# 10BASE-T1L_2.net
KiCad netlist of a schematic drawn in EAGLE
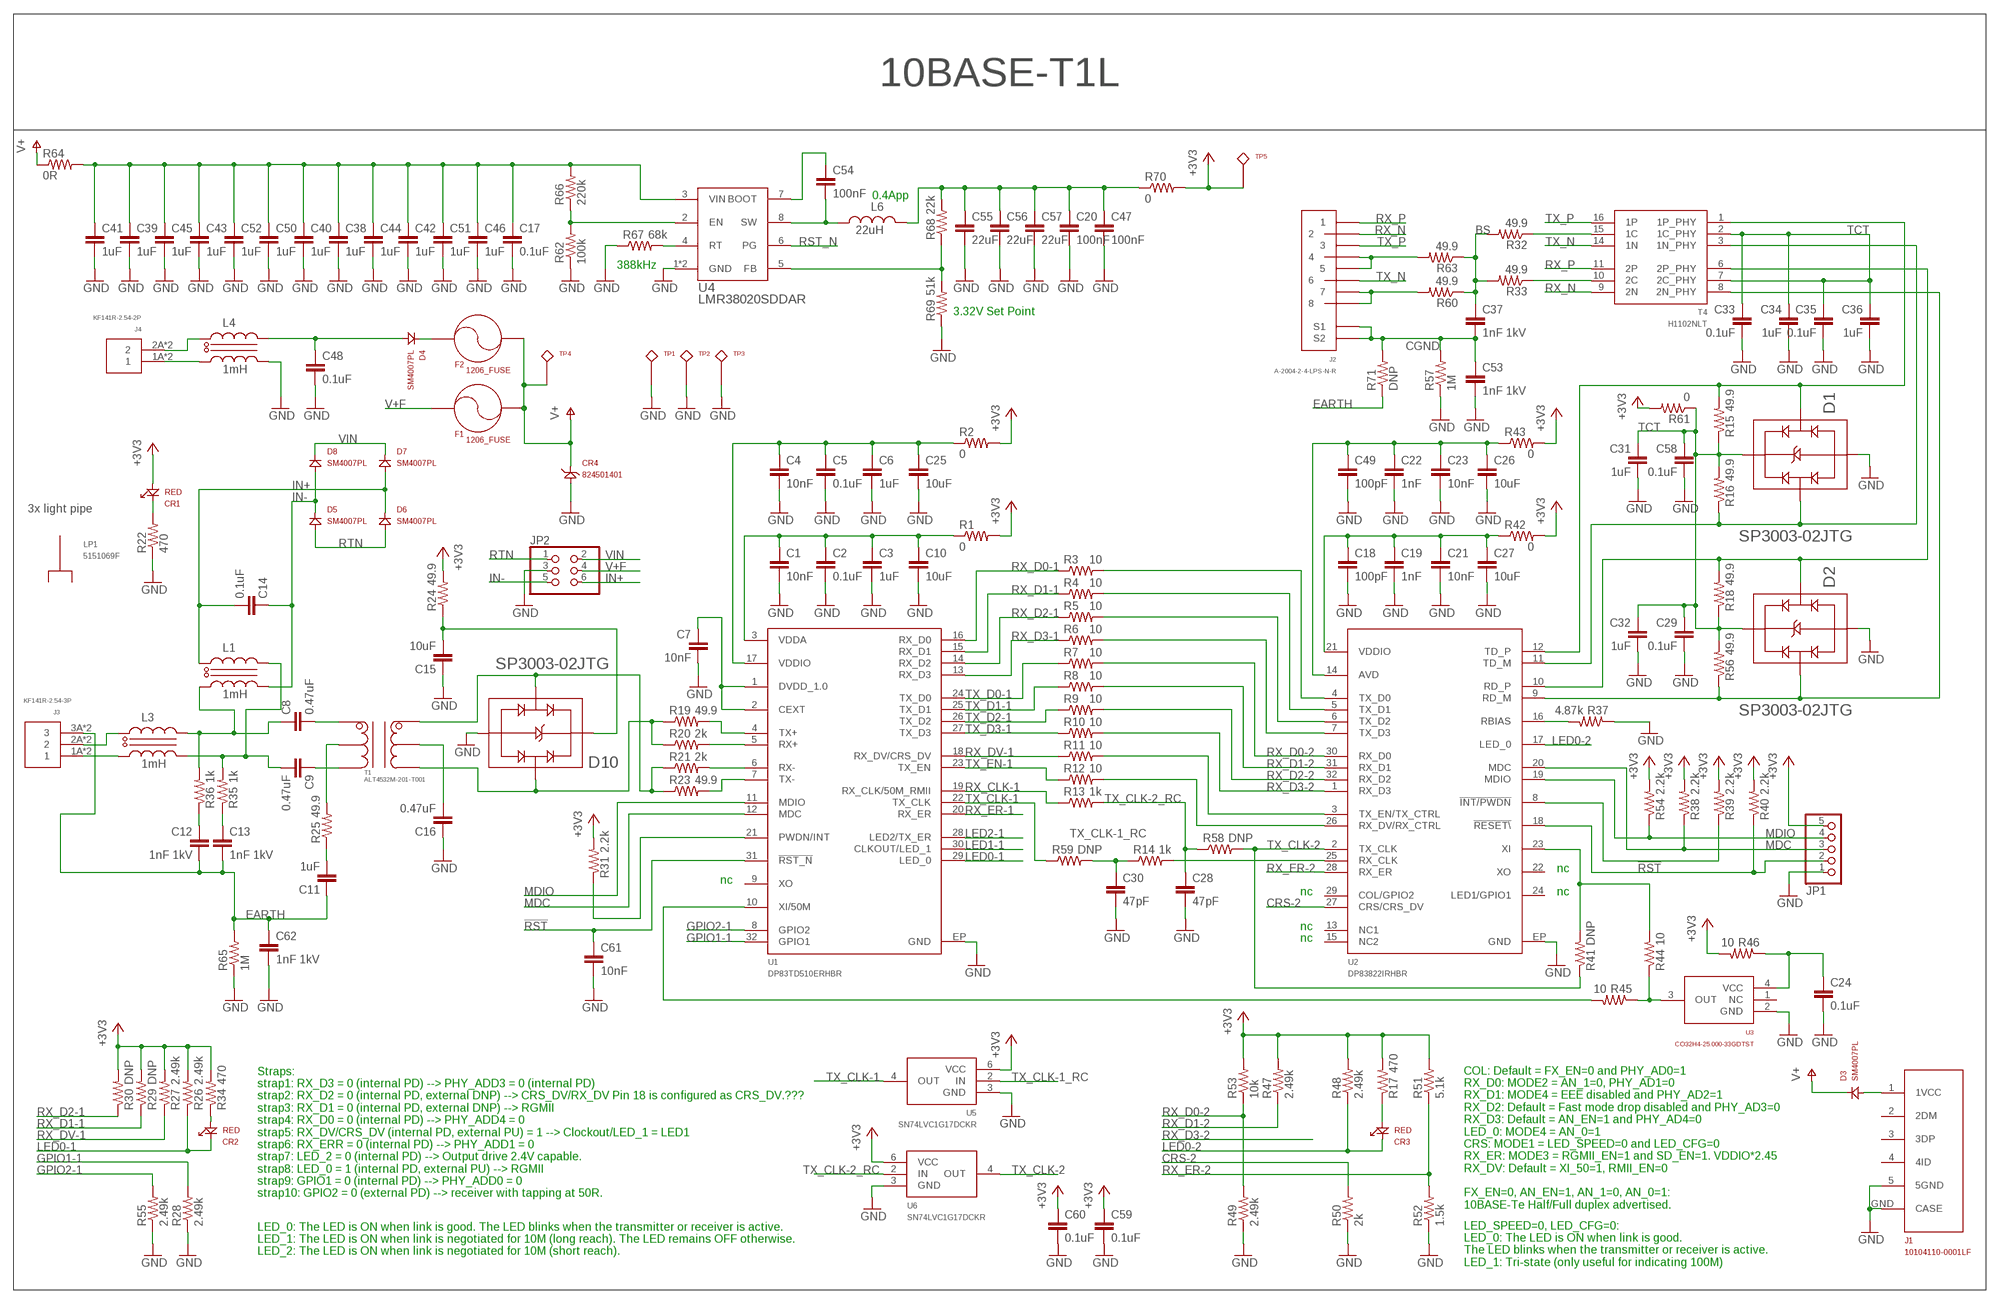
[diagram p0: schematic, sheet 1]

(export (version "E")
  (design (tool "Eeschema 10.0.6"))
  (components
    (comp (ref "C1")
      (value "10nF")
      (footprint "eagle-import:0402_INDUCTOR")
      (libsource (lib "eagle-import") (part "0402_CAPACITOR"))
    )
    (comp (ref "C2")
      (value "0.1uF")
      (footprint "eagle-import:0402_INDUCTOR")
      (libsource (lib "eagle-import") (part "0402_CAPACITOR"))
    )
    (comp (ref "C3")
      (value "1uF")
      (footprint "eagle-import:0402_INDUCTOR")
      (libsource (lib "eagle-import") (part "0402_CAPACITOR"))
    )
    (comp (ref "C4")
      (value "10nF")
      (footprint "eagle-import:0402_INDUCTOR")
      (libsource (lib "eagle-import") (part "0402_CAPACITOR"))
    )
    (comp (ref "C5")
      (value "0.1uF")
      (footprint "eagle-import:0402_INDUCTOR")
      (libsource (lib "eagle-import") (part "0402_CAPACITOR"))
    )
    (comp (ref "C6")
      (value "1uF")
      (footprint "eagle-import:0402_INDUCTOR")
      (libsource (lib "eagle-import") (part "0402_CAPACITOR"))
    )
    (comp (ref "C7")
      (value "10nF")
      (footprint "eagle-import:0402_INDUCTOR")
      (libsource (lib "eagle-import") (part "0402_CAPACITOR"))
    )
    (comp (ref "C8")
      (value "0.47uF")
      (footprint "eagle-import:0603")
      (libsource (lib "eagle-import") (part "0603_CAPACITOR"))
    )
    (comp (ref "C9")
      (value "0.47uF")
      (footprint "eagle-import:0603")
      (libsource (lib "eagle-import") (part "0603_CAPACITOR"))
    )
    (comp (ref "C10")
      (value "10uF")
      (footprint "eagle-import:0603")
      (libsource (lib "eagle-import") (part "0603_CAPACITOR"))
    )
    (comp (ref "C11")
      (value "1uF")
      (footprint "eagle-import:0603")
      (libsource (lib "eagle-import") (part "0603_CAPACITOR"))
    )
    (comp (ref "C12")
      (value "1nF 1kV")
      (footprint "eagle-import:C1206")
      (libsource (lib "eagle-import") (part "C-EUC1206"))
    )
    (comp (ref "C13")
      (value "1nF 1kV")
      (footprint "eagle-import:C1206")
      (libsource (lib "eagle-import") (part "C-EUC1206"))
    )
    (comp (ref "C14")
      (value "0.1uF")
      (footprint "eagle-import:0603")
      (libsource (lib "eagle-import") (part "0603_CAPACITOR"))
    )
    (comp (ref "C15")
      (value "10uF")
      (footprint "eagle-import:0603")
      (libsource (lib "eagle-import") (part "0603_CAPACITOR"))
    )
    (comp (ref "C16")
      (value "0.47uF")
      (footprint "eagle-import:0603")
      (libsource (lib "eagle-import") (part "0603_CAPACITOR"))
    )
    (comp (ref "C17")
      (value "0.1uF")
      (footprint "eagle-import:0603")
      (libsource (lib "eagle-import") (part "0603_CAPACITOR"))
    )
    (comp (ref "C18")
      (value "100pF")
      (footprint "eagle-import:0402_INDUCTOR")
      (libsource (lib "eagle-import") (part "0402_CAPACITOR"))
    )
    (comp (ref "C19")
      (value "1nF")
      (footprint "eagle-import:0402_INDUCTOR")
      (libsource (lib "eagle-import") (part "0402_CAPACITOR"))
    )
    (comp (ref "C20")
      (value "100nF")
      (footprint "eagle-import:0603")
      (libsource (lib "eagle-import") (part "0603_CAPACITOR"))
    )
    (comp (ref "C21")
      (value "10nF")
      (footprint "eagle-import:0402_INDUCTOR")
      (libsource (lib "eagle-import") (part "0402_CAPACITOR"))
    )
    (comp (ref "C22")
      (value "1nF")
      (footprint "eagle-import:0402_INDUCTOR")
      (libsource (lib "eagle-import") (part "0402_CAPACITOR"))
    )
    (comp (ref "C23")
      (value "10nF")
      (footprint "eagle-import:0402_INDUCTOR")
      (libsource (lib "eagle-import") (part "0402_CAPACITOR"))
    )
    (comp (ref "C24")
      (value "0.1uF")
      (footprint "eagle-import:0402_INDUCTOR")
      (libsource (lib "eagle-import") (part "0402_CAPACITOR"))
    )
    (comp (ref "C25")
      (value "10uF")
      (footprint "eagle-import:0603")
      (libsource (lib "eagle-import") (part "0603_CAPACITOR"))
    )
    (comp (ref "C26")
      (value "10uF")
      (footprint "eagle-import:0603")
      (libsource (lib "eagle-import") (part "0603_CAPACITOR"))
    )
    (comp (ref "C27")
      (value "10uF")
      (footprint "eagle-import:0603")
      (libsource (lib "eagle-import") (part "0603_CAPACITOR"))
    )
    (comp (ref "C28")
      (value "47pF")
      (footprint "eagle-import:0402_INDUCTOR")
      (libsource (lib "eagle-import") (part "0402_CAPACITOR"))
    )
    (comp (ref "C29")
      (value "0.1uF")
      (footprint "eagle-import:0402_INDUCTOR")
      (libsource (lib "eagle-import") (part "0402_CAPACITOR"))
    )
    (comp (ref "C30")
      (value "47pF")
      (footprint "eagle-import:0402_INDUCTOR")
      (libsource (lib "eagle-import") (part "0402_CAPACITOR"))
    )
    (comp (ref "C31")
      (value "1uF")
      (footprint "eagle-import:0402_INDUCTOR")
      (libsource (lib "eagle-import") (part "0402_CAPACITOR"))
    )
    (comp (ref "C32")
      (value "1uF")
      (footprint "eagle-import:0402_INDUCTOR")
      (libsource (lib "eagle-import") (part "0402_CAPACITOR"))
    )
    (comp (ref "C33")
      (value "0.1uF")
      (footprint "eagle-import:0402_INDUCTOR")
      (libsource (lib "eagle-import") (part "0402_CAPACITOR"))
    )
    (comp (ref "C34")
      (value "1uF")
      (footprint "eagle-import:0402_INDUCTOR")
      (libsource (lib "eagle-import") (part "0402_CAPACITOR"))
    )
    (comp (ref "C35")
      (value "0.1uF")
      (footprint "eagle-import:0402_INDUCTOR")
      (libsource (lib "eagle-import") (part "0402_CAPACITOR"))
    )
    (comp (ref "C36")
      (value "1uF")
      (footprint "eagle-import:0402_INDUCTOR")
      (libsource (lib "eagle-import") (part "0402_CAPACITOR"))
    )
    (comp (ref "C37")
      (value "1nF 1kV")
      (footprint "eagle-import:C1206")
      (libsource (lib "eagle-import") (part "C-EUC1206"))
    )
    (comp (ref "C38")
      (value "1uF")
      (footprint "eagle-import:C1206")
      (libsource (lib "eagle-import") (part "C-EUC1206"))
    )
    (comp (ref "C39")
      (value "1uF")
      (footprint "eagle-import:C1206")
      (libsource (lib "eagle-import") (part "C-EUC1206"))
    )
    (comp (ref "C40")
      (value "1uF")
      (footprint "eagle-import:C1206")
      (libsource (lib "eagle-import") (part "C-EUC1206"))
    )
    (comp (ref "C41")
      (value "1uF")
      (footprint "eagle-import:C1206")
      (libsource (lib "eagle-import") (part "C-EUC1206"))
    )
    (comp (ref "C42")
      (value "1uF")
      (footprint "eagle-import:C1206")
      (libsource (lib "eagle-import") (part "C-EUC1206"))
    )
    (comp (ref "C43")
      (value "1uF")
      (footprint "eagle-import:C1206")
      (libsource (lib "eagle-import") (part "C-EUC1206"))
    )
    (comp (ref "C44")
      (value "1uF")
      (footprint "eagle-import:C1206")
      (libsource (lib "eagle-import") (part "C-EUC1206"))
    )
    (comp (ref "C45")
      (value "1uF")
      (footprint "eagle-import:C1206")
      (libsource (lib "eagle-import") (part "C-EUC1206"))
    )
    (comp (ref "C46")
      (value "1uF")
      (footprint "eagle-import:C1206")
      (libsource (lib "eagle-import") (part "C-EUC1206"))
    )
    (comp (ref "C47")
      (value "100nF")
      (footprint "eagle-import:0603")
      (libsource (lib "eagle-import") (part "0603_CAPACITOR"))
    )
    (comp (ref "C48")
      (value "0.1uF")
      (footprint "eagle-import:0603")
      (libsource (lib "eagle-import") (part "0603_CAPACITOR"))
    )
    (comp (ref "C49")
      (value "100pF")
      (footprint "eagle-import:0402_INDUCTOR")
      (libsource (lib "eagle-import") (part "0402_CAPACITOR"))
    )
    (comp (ref "C50")
      (value "1uF")
      (footprint "eagle-import:C1206")
      (libsource (lib "eagle-import") (part "C-EUC1206"))
    )
    (comp (ref "C51")
      (value "1uF")
      (footprint "eagle-import:C1206")
      (libsource (lib "eagle-import") (part "C-EUC1206"))
    )
    (comp (ref "C52")
      (value "1uF")
      (footprint "eagle-import:C1206")
      (libsource (lib "eagle-import") (part "C-EUC1206"))
    )
    (comp (ref "C53")
      (value "1nF 1kV")
      (footprint "eagle-import:C1206")
      (libsource (lib "eagle-import") (part "C-EUC1206"))
    )
    (comp (ref "C54")
      (value "100nF")
      (footprint "eagle-import:0603")
      (libsource (lib "eagle-import") (part "0603_CAPACITOR"))
    )
    (comp (ref "C55")
      (value "22uF")
      (footprint "eagle-import:C1206")
      (libsource (lib "eagle-import") (part "C-EUC1206"))
    )
    (comp (ref "C56")
      (value "22uF")
      (footprint "eagle-import:C1206")
      (libsource (lib "eagle-import") (part "C-EUC1206"))
    )
    (comp (ref "C57")
      (value "22uF")
      (footprint "eagle-import:C1206")
      (libsource (lib "eagle-import") (part "C-EUC1206"))
    )
    (comp (ref "C58")
      (value "0.1uF")
      (footprint "eagle-import:0402_INDUCTOR")
      (libsource (lib "eagle-import") (part "0402_CAPACITOR"))
    )
    (comp (ref "C59")
      (value "0.1uF")
      (footprint "eagle-import:0402_INDUCTOR")
      (libsource (lib "eagle-import") (part "0402_CAPACITOR"))
    )
    (comp (ref "C60")
      (value "0.1uF")
      (footprint "eagle-import:0402_INDUCTOR")
      (libsource (lib "eagle-import") (part "0402_CAPACITOR"))
    )
    (comp (ref "C61")
      (value "10nF")
      (footprint "eagle-import:0402_INDUCTOR")
      (libsource (lib "eagle-import") (part "0402_CAPACITOR"))
    )
    (comp (ref "C62")
      (value "1nF 1kV")
      (footprint "eagle-import:C1206")
      (libsource (lib "eagle-import") (part "C-EUC1206"))
    )
    (comp (ref "CR1")
      (value "RED")
      (footprint "eagle-import:0603_DIODE")
      (fields (field (name "PARTNO") "732-4978-1-ND"))
      (libsource (lib "eagle-import") (part "150060RS75000"))
    )
    (comp (ref "CR2")
      (value "RED")
      (footprint "eagle-import:0603_DIODE")
      (fields (field (name "PARTNO") "732-4978-1-ND"))
      (libsource (lib "eagle-import") (part "150060RS75000"))
    )
    (comp (ref "CR3")
      (value "RED")
      (footprint "eagle-import:0603_DIODE")
      (fields (field (name "PARTNO") "732-4978-1-ND"))
      (libsource (lib "eagle-import") (part "150060RS75000"))
    )
    (comp (ref "CR4")
      (value "824501401")
      (footprint "eagle-import:DO-214AC")
      (fields (field (name "PARTNO") "732-9960-1-ND"))
      (libsource (lib "eagle-import") (part "824501401"))
    )
    (comp (ref "D1")
      (value "SP3003-02JTG")
      (footprint "eagle-import:SC-70-5")
      (fields (field (name "PARTNO") "F3301CT-ND"))
      (libsource (lib "eagle-import") (part "SP3003-02JTG"))
    )
    (comp (ref "D2")
      (value "SP3003-02JTG")
      (footprint "eagle-import:SC-70-5")
      (fields (field (name "PARTNO") "F3301CT-ND"))
      (libsource (lib "eagle-import") (part "SP3003-02JTG"))
    )
    (comp (ref "D3")
      (value "SM4007PL")
      (footprint "eagle-import:SOD123(AK)")
      (libsource (lib "eagle-import") (part "SM4007PL"))
    )
    (comp (ref "D4")
      (value "SM4007PL")
      (footprint "eagle-import:SOD123(AK)")
      (libsource (lib "eagle-import") (part "SM4007PL"))
    )
    (comp (ref "D5")
      (value "SM4007PL")
      (footprint "eagle-import:SOD123(AK)")
      (libsource (lib "eagle-import") (part "SM4007PL"))
    )
    (comp (ref "D6")
      (value "SM4007PL")
      (footprint "eagle-import:SOD123(AK)")
      (libsource (lib "eagle-import") (part "SM4007PL"))
    )
    (comp (ref "D7")
      (value "SM4007PL")
      (footprint "eagle-import:SOD123(AK)")
      (libsource (lib "eagle-import") (part "SM4007PL"))
    )
    (comp (ref "D8")
      (value "SM4007PL")
      (footprint "eagle-import:SOD123(AK)")
      (libsource (lib "eagle-import") (part "SM4007PL"))
    )
    (comp (ref "D10")
      (value "SP3003-02JTG")
      (footprint "eagle-import:SC-70-5")
      (fields (field (name "PARTNO") "F3301CT-ND"))
      (libsource (lib "eagle-import") (part "SP3003-02JTG"))
    )
    (comp (ref "F1")
      (value "1206_FUSE")
      (footprint "eagle-import:1206")
      (libsource (lib "eagle-import") (part "1206_FUSE"))
    )
    (comp (ref "F2")
      (value "1206_FUSE")
      (footprint "eagle-import:1206")
      (libsource (lib "eagle-import") (part "1206_FUSE"))
    )
    (comp (ref "J1")
      (value "10104110-0001LF")
      (footprint "eagle-import:MICRO_USB")
      (fields (field (name "PARTNO") "609-4052-1-ND"))
      (libsource (lib "eagle-import") (part "10104110-0001LF"))
    )
    (comp (ref "J2")
      (value "A-2004-2-4-LPS-N-R")
      (footprint "eagle-import:A-2004-2-4-LPS-N-R")
      (fields (field (name "PARTNO") "AE10387-ND"))
      (libsource (lib "eagle-import") (part "A-2004-2-4-LPS-N-R"))
    )
    (comp (ref "J3")
      (value "KF141R-2.54-3P")
      (footprint "eagle-import:KF141R-2.54-3P")
      (libsource (lib "eagle-import") (part "KF141R-2.54-3P"))
    )
    (comp (ref "J4")
      (value "KF141R-2.54-2P")
      (footprint "eagle-import:KF141R-2.54-2P")
      (libsource (lib "eagle-import") (part "KF141R-2.54-2P"))
    )
    (comp (ref "JP1")
      (value "PINHD-1X5")
      (footprint "eagle-import:1X05")
      (libsource (lib "eagle-import") (part "PINHD-1X5"))
    )
    (comp (ref "JP2")
      (value "PINHD-2X3")
      (footprint "eagle-import:2X03")
      (libsource (lib "eagle-import") (part "PINHD-2X3"))
    )
    (comp (ref "L1")
      (value "1mH")
      (footprint "eagle-import:SMCM090605")
      (libsource (lib "eagle-import") (part "SMCM090605-102"))
    )
    (comp (ref "L3")
      (value "1mH")
      (footprint "eagle-import:SMCM090605")
      (libsource (lib "eagle-import") (part "SMCM090605-102"))
    )
    (comp (ref "L4")
      (value "1mH")
      (footprint "eagle-import:SMCM090605")
      (libsource (lib "eagle-import") (part "SMCM090605-102"))
    )
    (comp (ref "L6")
      (value "22uH")
      (footprint "eagle-import:TMPC0603H")
      (libsource (lib "eagle-import") (part "TMPC0603H-220MG-D"))
    )
    (comp (ref "LP1")
      (value "5151069F")
      (footprint "eagle-import:5151069F")
      (fields (field (name "PARTNO") "350-2182-ND"))
      (libsource (lib "eagle-import") (part "5151069F"))
    )
    (comp (ref "R1")
      (value "0")
      (footprint "eagle-import:0603")
      (libsource (lib "eagle-import") (part "0603_RESISTOR"))
    )
    (comp (ref "R2")
      (value "0")
      (footprint "eagle-import:0603")
      (libsource (lib "eagle-import") (part "0603_RESISTOR"))
    )
    (comp (ref "R3")
      (value "10")
      (footprint "eagle-import:R0402")
      (libsource (lib "eagle-import") (part "0402_RESISTOR"))
    )
    (comp (ref "R4")
      (value "10")
      (footprint "eagle-import:R0402")
      (libsource (lib "eagle-import") (part "0402_RESISTOR"))
    )
    (comp (ref "R5")
      (value "10")
      (footprint "eagle-import:R0402")
      (libsource (lib "eagle-import") (part "0402_RESISTOR"))
    )
    (comp (ref "R6")
      (value "10")
      (footprint "eagle-import:R0402")
      (libsource (lib "eagle-import") (part "0402_RESISTOR"))
    )
    (comp (ref "R7")
      (value "10")
      (footprint "eagle-import:R0402")
      (libsource (lib "eagle-import") (part "0402_RESISTOR"))
    )
    (comp (ref "R8")
      (value "10")
      (footprint "eagle-import:R0402")
      (libsource (lib "eagle-import") (part "0402_RESISTOR"))
    )
    (comp (ref "R9")
      (value "10")
      (footprint "eagle-import:R0402")
      (libsource (lib "eagle-import") (part "0402_RESISTOR"))
    )
    (comp (ref "R10")
      (value "10")
      (footprint "eagle-import:R0402")
      (libsource (lib "eagle-import") (part "0402_RESISTOR"))
    )
    (comp (ref "R11")
      (value "10")
      (footprint "eagle-import:R0402")
      (libsource (lib "eagle-import") (part "0402_RESISTOR"))
    )
    (comp (ref "R12")
      (value "10")
      (footprint "eagle-import:R0402")
      (libsource (lib "eagle-import") (part "0402_RESISTOR"))
    )
    (comp (ref "R13")
      (value "1k")
      (footprint "eagle-import:R0402")
      (libsource (lib "eagle-import") (part "0402_RESISTOR"))
    )
    (comp (ref "R14")
      (value "1k")
      (footprint "eagle-import:R0402")
      (libsource (lib "eagle-import") (part "0402_RESISTOR"))
    )
    (comp (ref "R15")
      (value "49.9")
      (footprint "eagle-import:R0402")
      (libsource (lib "eagle-import") (part "0402_RESISTOR"))
    )
    (comp (ref "R16")
      (value "49.9")
      (footprint "eagle-import:R0402")
      (libsource (lib "eagle-import") (part "0402_RESISTOR"))
    )
    (comp (ref "R17")
      (value "470")
      (footprint "eagle-import:0603")
      (libsource (lib "eagle-import") (part "0603_RESISTOR"))
    )
    (comp (ref "R18")
      (value "49.9")
      (footprint "eagle-import:R0402")
      (libsource (lib "eagle-import") (part "0402_RESISTOR"))
    )
    (comp (ref "R19")
      (value "49.9")
      (footprint "eagle-import:R0402")
      (libsource (lib "eagle-import") (part "0402_RESISTOR"))
    )
    (comp (ref "R20")
      (value "2k")
      (footprint "eagle-import:R0402")
      (libsource (lib "eagle-import") (part "0402_RESISTOR"))
    )
    (comp (ref "R21")
      (value "2k")
      (footprint "eagle-import:R0402")
      (libsource (lib "eagle-import") (part "0402_RESISTOR"))
    )
    (comp (ref "R22")
      (value "470")
      (footprint "eagle-import:0603")
      (libsource (lib "eagle-import") (part "0603_RESISTOR"))
    )
    (comp (ref "R23")
      (value "49.9")
      (footprint "eagle-import:R0402")
      (libsource (lib "eagle-import") (part "0402_RESISTOR"))
    )
    (comp (ref "R24")
      (value "49.9")
      (footprint "eagle-import:0603")
      (libsource (lib "eagle-import") (part "0603_RESISTOR"))
    )
    (comp (ref "R25")
      (value "49.9")
      (footprint "eagle-import:0603")
      (libsource (lib "eagle-import") (part "0603_RESISTOR"))
    )
    (comp (ref "R26")
      (value "2.49k")
      (footprint "eagle-import:R0402")
      (libsource (lib "eagle-import") (part "0402_RESISTOR"))
    )
    (comp (ref "R27")
      (value "2.49k")
      (footprint "eagle-import:R0402")
      (libsource (lib "eagle-import") (part "0402_RESISTOR"))
    )
    (comp (ref "R28")
      (value "2.49k")
      (footprint "eagle-import:R0402")
      (libsource (lib "eagle-import") (part "0402_RESISTOR"))
    )
    (comp (ref "R29")
      (value "DNP")
      (footprint "eagle-import:R0402")
      (libsource (lib "eagle-import") (part "0402_RESISTOR"))
    )
    (comp (ref "R30")
      (value "DNP")
      (footprint "eagle-import:R0402")
      (libsource (lib "eagle-import") (part "0402_RESISTOR"))
    )
    (comp (ref "R31")
      (value "2.2k")
      (footprint "eagle-import:R0402")
      (libsource (lib "eagle-import") (part "0402_RESISTOR"))
    )
    (comp (ref "R32")
      (value "49.9")
      (footprint "eagle-import:R0402")
      (libsource (lib "eagle-import") (part "0402_RESISTOR"))
    )
    (comp (ref "R33")
      (value "49.9")
      (footprint "eagle-import:R0402")
      (libsource (lib "eagle-import") (part "0402_RESISTOR"))
    )
    (comp (ref "R34")
      (value "470")
      (footprint "eagle-import:0603")
      (libsource (lib "eagle-import") (part "0603_RESISTOR"))
    )
    (comp (ref "R35")
      (value "1k")
      (footprint "eagle-import:0603")
      (libsource (lib "eagle-import") (part "0603_RESISTOR"))
    )
    (comp (ref "R36")
      (value "1k")
      (footprint "eagle-import:0603")
      (libsource (lib "eagle-import") (part "0603_RESISTOR"))
    )
    (comp (ref "R37")
      (value "4.87k")
      (footprint "eagle-import:R0402")
      (libsource (lib "eagle-import") (part "0402_RESISTOR"))
    )
    (comp (ref "R38")
      (value "2.2k")
      (footprint "eagle-import:R0402")
      (libsource (lib "eagle-import") (part "0402_RESISTOR"))
    )
    (comp (ref "R39")
      (value "2.2k")
      (footprint "eagle-import:R0402")
      (libsource (lib "eagle-import") (part "0402_RESISTOR"))
    )
    (comp (ref "R40")
      (value "2.2k")
      (footprint "eagle-import:R0402")
      (libsource (lib "eagle-import") (part "0402_RESISTOR"))
    )
    (comp (ref "R41")
      (value "DNP")
      (footprint "eagle-import:R0402")
      (libsource (lib "eagle-import") (part "0402_RESISTOR"))
    )
    (comp (ref "R42")
      (value "0")
      (footprint "eagle-import:0603")
      (libsource (lib "eagle-import") (part "0603_RESISTOR"))
    )
    (comp (ref "R43")
      (value "0")
      (footprint "eagle-import:0603")
      (libsource (lib "eagle-import") (part "0603_RESISTOR"))
    )
    (comp (ref "R44")
      (value "10")
      (footprint "eagle-import:R0402")
      (libsource (lib "eagle-import") (part "0402_RESISTOR"))
    )
    (comp (ref "R45")
      (value "10")
      (footprint "eagle-import:R0402")
      (libsource (lib "eagle-import") (part "0402_RESISTOR"))
    )
    (comp (ref "R46")
      (value "10")
      (footprint "eagle-import:R0402")
      (libsource (lib "eagle-import") (part "0402_RESISTOR"))
    )
    (comp (ref "R47")
      (value "2.49k")
      (footprint "eagle-import:R0402")
      (libsource (lib "eagle-import") (part "0402_RESISTOR"))
    )
    (comp (ref "R48")
      (value "2.49k")
      (footprint "eagle-import:R0402")
      (libsource (lib "eagle-import") (part "0402_RESISTOR"))
    )
    (comp (ref "R49")
      (value "2.49k")
      (footprint "eagle-import:R0402")
      (libsource (lib "eagle-import") (part "0402_RESISTOR"))
    )
    (comp (ref "R50")
      (value "2k")
      (footprint "eagle-import:R0402")
      (libsource (lib "eagle-import") (part "0402_RESISTOR"))
    )
    (comp (ref "R51")
      (value "5.1k")
      (footprint "eagle-import:R0402")
      (libsource (lib "eagle-import") (part "0402_RESISTOR"))
    )
    (comp (ref "R52")
      (value "1.5k")
      (footprint "eagle-import:R0402")
      (libsource (lib "eagle-import") (part "0402_RESISTOR"))
    )
    (comp (ref "R53")
      (value "10k")
      (footprint "eagle-import:R0402")
      (libsource (lib "eagle-import") (part "0402_RESISTOR"))
    )
    (comp (ref "R54")
      (value "2.2k")
      (footprint "eagle-import:R0402")
      (libsource (lib "eagle-import") (part "0402_RESISTOR"))
    )
    (comp (ref "R55")
      (value "2.49k")
      (footprint "eagle-import:R0402")
      (libsource (lib "eagle-import") (part "0402_RESISTOR"))
    )
    (comp (ref "R56")
      (value "49.9")
      (footprint "eagle-import:R0402")
      (libsource (lib "eagle-import") (part "0402_RESISTOR"))
    )
    (comp (ref "R57")
      (value "1M")
      (footprint "eagle-import:1206")
      (libsource (lib "eagle-import") (part "1206_RESISTOR"))
    )
    (comp (ref "R58")
      (value "DNP")
      (footprint "eagle-import:R0402")
      (libsource (lib "eagle-import") (part "0402_RESISTOR"))
    )
    (comp (ref "R59")
      (value "DNP")
      (footprint "eagle-import:R0402")
      (libsource (lib "eagle-import") (part "0402_RESISTOR"))
    )
    (comp (ref "R60")
      (value "49.9")
      (footprint "eagle-import:R0402")
      (libsource (lib "eagle-import") (part "0402_RESISTOR"))
    )
    (comp (ref "R61")
      (value "0")
      (footprint "eagle-import:0603")
      (libsource (lib "eagle-import") (part "0603_RESISTOR"))
    )
    (comp (ref "R62")
      (value "100k")
      (footprint "eagle-import:0603")
      (libsource (lib "eagle-import") (part "0603_RESISTOR"))
    )
    (comp (ref "R63")
      (value "49.9")
      (footprint "eagle-import:R0402")
      (libsource (lib "eagle-import") (part "0402_RESISTOR"))
    )
    (comp (ref "R64")
      (value "0R")
      (footprint "eagle-import:1206")
      (libsource (lib "eagle-import") (part "1206_RESISTOR"))
    )
    (comp (ref "R65")
      (value "1M")
      (footprint "eagle-import:1206")
      (libsource (lib "eagle-import") (part "1206_RESISTOR"))
    )
    (comp (ref "R66")
      (value "220k")
      (footprint "eagle-import:0603")
      (libsource (lib "eagle-import") (part "0603_RESISTOR"))
    )
    (comp (ref "R67")
      (value "68k")
      (footprint "eagle-import:0603")
      (libsource (lib "eagle-import") (part "0603_RESISTOR"))
    )
    (comp (ref "R68")
      (value "22k")
      (footprint "eagle-import:0603")
      (libsource (lib "eagle-import") (part "0603_RESISTOR"))
    )
    (comp (ref "R69")
      (value "51k")
      (footprint "eagle-import:0603")
      (libsource (lib "eagle-import") (part "0603_RESISTOR"))
    )
    (comp (ref "R70")
      (value "0")
      (footprint "eagle-import:0603")
      (libsource (lib "eagle-import") (part "0603_RESISTOR"))
    )
    (comp (ref "R71")
      (value "DNP")
      (footprint "eagle-import:0603")
      (libsource (lib "eagle-import") (part "0603_RESISTOR"))
    )
    (comp (ref "T1")
      (value "ALT4532M-201-T001")
      (footprint "eagle-import:TDK_ALT")
      (fields (field (name "PARTNO") "445-15085-1-ND"))
      (libsource (lib "eagle-import") (part "ALT4532M-201-T001"))
    )
    (comp (ref "T4")
      (value "H1102NLT")
      (footprint "eagle-import:H1102NLT")
      (libsource (lib "eagle-import") (part "H1102NLT"))
    )
    (comp (ref "TP1")
      (value "5011")
      (footprint "eagle-import:5010")
      (fields (field (name "PARTNO") "36-5011-ND"))
      (libsource (lib "eagle-import") (part "5011"))
    )
    (comp (ref "TP2")
      (value "5011")
      (footprint "eagle-import:5010")
      (fields (field (name "PARTNO") "36-5011-ND"))
      (libsource (lib "eagle-import") (part "5011"))
    )
    (comp (ref "TP3")
      (value "5011")
      (footprint "eagle-import:5010")
      (fields (field (name "PARTNO") "36-5011-ND"))
      (libsource (lib "eagle-import") (part "5011"))
    )
    (comp (ref "TP4")
      (value "5010")
      (footprint "eagle-import:5010")
      (fields (field (name "PARTNO") "36-5010-ND"))
      (libsource (lib "eagle-import") (part "5010"))
    )
    (comp (ref "TP5")
      (value "5010")
      (footprint "eagle-import:5010")
      (fields (field (name "PARTNO") "36-5010-ND"))
      (libsource (lib "eagle-import") (part "5010"))
    )
    (comp (ref "U1")
      (value "DP83TD510ERHBR")
      (footprint "eagle-import:QFN32-55_TI")
      (fields (field (name "PARTNO") "296-DP83TD510ERHBRCT-ND"))
      (libsource (lib "eagle-import") (part "DP83TD510ERHBR"))
    )
    (comp (ref "U2")
      (value "DP83822IRHBR")
      (footprint "eagle-import:QFN32-55_TI")
      (fields (field (name "PARTNO") "296-44794-1-ND"))
      (libsource (lib "eagle-import") (part "DP83822IRHBR"))
    )
    (comp (ref "U3")
      (value "CO32H4-25.000-33GDTST")
      (footprint "eagle-import:3.2X2.5_4SMD")
      (libsource (lib "eagle-import") (part "CO32H4-25.000-33GDTST"))
    )
    (comp (ref "U4")
      (value "LMR38020SDDAR")
      (footprint "eagle-import:SOIC8_TP_TI")
      (fields (field (name "PARTNO") "296-LMR38020SDDARCT-ND"))
      (libsource (lib "eagle-import") (part "LMR38020SDDAR"))
    )
    (comp (ref "U5")
      (value "SN74LVC1G17DCKR")
      (footprint "eagle-import:SC-70")
      (fields (field (name "PARTNO") "296-11934-1-ND"))
      (libsource (lib "eagle-import") (part "SN74LVC1G17DCKR"))
    )
    (comp (ref "U6")
      (value "SN74LVC1G17DCKR")
      (footprint "eagle-import:SC-70")
      (fields (field (name "PARTNO") "296-11934-1-ND"))
      (libsource (lib "eagle-import") (part "SN74LVC1G17DCKR"))
    )
  )
  (nets
    (net (code "1") (name "+3V3") (class "Default")
      (node (ref "C59") (pin "P$1") (pinfunction "1_P$1") (pintype "passive"))
      (node (ref "C60") (pin "P$1") (pinfunction "1_P$1") (pintype "passive"))
      (node (ref "CR1") (pin "A") (pinfunction "A_A") (pintype "bidirectional"))
      (node (ref "JP1") (pin "5") (pinfunction "5_5") (pintype "passive"))
      (node (ref "R1") (pin "2") (pinfunction "2_2") (pintype "passive"))
      (node (ref "R17") (pin "2") (pinfunction "2_2") (pintype "passive"))
      (node (ref "R2") (pin "2") (pinfunction "2_2") (pintype "passive"))
      (node (ref "R24") (pin "2") (pinfunction "2_2") (pintype "passive"))
      (node (ref "R26") (pin "2") (pinfunction "2_2") (pintype "passive"))
      (node (ref "R27") (pin "2") (pinfunction "2_2") (pintype "passive"))
      (node (ref "R29") (pin "2") (pinfunction "2_2") (pintype "passive"))
      (node (ref "R30") (pin "2") (pinfunction "2_2") (pintype "passive"))
      (node (ref "R31") (pin "2") (pinfunction "2_2") (pintype "passive"))
      (node (ref "R34") (pin "2") (pinfunction "2_2") (pintype "passive"))
      (node (ref "R38") (pin "2") (pinfunction "2_2") (pintype "passive"))
      (node (ref "R39") (pin "2") (pinfunction "2_2") (pintype "passive"))
      (node (ref "R40") (pin "2") (pinfunction "2_2") (pintype "passive"))
      (node (ref "R42") (pin "2") (pinfunction "2_2") (pintype "passive"))
      (node (ref "R43") (pin "2") (pinfunction "2_2") (pintype "passive"))
      (node (ref "R46") (pin "2") (pinfunction "2_2") (pintype "passive"))
      (node (ref "R47") (pin "2") (pinfunction "2_2") (pintype "passive"))
      (node (ref "R48") (pin "2") (pinfunction "2_2") (pintype "passive"))
      (node (ref "R51") (pin "2") (pinfunction "2_2") (pintype "passive"))
      (node (ref "R53") (pin "2") (pinfunction "2_2") (pintype "passive"))
      (node (ref "R54") (pin "2") (pinfunction "2_2") (pintype "passive"))
      (node (ref "R61") (pin "2") (pinfunction "2_2") (pintype "passive"))
      (node (ref "R70") (pin "2") (pinfunction "2_2") (pintype "passive"))
      (node (ref "TP5") (pin "P$1") (pinfunction "P$1_P$1") (pintype "bidirectional"))
      (node (ref "U5") (pin "6") (pinfunction "VCC_6") (pintype "bidirectional"))
      (node (ref "U6") (pin "6") (pinfunction "VCC_6") (pintype "bidirectional"))
    )
    (net (code "2") (name "BS") (class "Default")
      (node (ref "C37") (pin "1") (pinfunction "1_1") (pintype "passive"))
      (node (ref "R32") (pin "2") (pinfunction "2_2") (pintype "passive"))
      (node (ref "R33") (pin "2") (pinfunction "2_2") (pintype "passive"))
      (node (ref "R60") (pin "1") (pinfunction "1_1") (pintype "passive"))
      (node (ref "R63") (pin "1") (pinfunction "1_1") (pintype "passive"))
    )
    (net (code "3") (name "CGND") (class "Default")
      (node (ref "C37") (pin "2") (pinfunction "2_2") (pintype "passive"))
      (node (ref "C53") (pin "1") (pinfunction "1_1") (pintype "passive"))
      (node (ref "J2") (pin "S1") (pinfunction "S1_S1") (pintype "bidirectional"))
      (node (ref "J2") (pin "S2") (pinfunction "S2_S2") (pintype "bidirectional"))
      (node (ref "R57") (pin "2") (pinfunction "2_2") (pintype "passive"))
      (node (ref "R71") (pin "2") (pinfunction "2_2") (pintype "passive"))
    )
    (net (code "4") (name "CRS-2") (class "Default")
      (node (ref "R50") (pin "2") (pinfunction "2_2") (pintype "passive"))
      (node (ref "U2") (pin "27") (pinfunction "CRS/CRS_DV_27") (pintype "bidirectional"))
    )
    (net (code "5") (name "EARTH") (class "Default")
      (node (ref "C11") (pin "1") (pinfunction "1_1") (pintype "passive"))
      (node (ref "C12") (pin "2") (pinfunction "2_2") (pintype "passive"))
      (node (ref "C13") (pin "2") (pinfunction "2_2") (pintype "passive"))
      (node (ref "C62") (pin "1") (pinfunction "1_1") (pintype "passive"))
      (node (ref "J3") (pin "3A") (pinfunction "3_3A") (pintype "bidirectional"))
      (node (ref "J3") (pin "3B") (pinfunction "3_3B") (pintype "bidirectional"))
      (node (ref "R65") (pin "2") (pinfunction "2_2") (pintype "passive"))
      (node (ref "R71") (pin "1") (pinfunction "1_1") (pintype "passive"))
    )
    (net (code "6") (name "GND") (class "Default")
      (node (ref "C1") (pin "P$2") (pinfunction "2_P$2") (pintype "passive"))
      (node (ref "C10") (pin "2") (pinfunction "2_2") (pintype "passive"))
      (node (ref "C15") (pin "1") (pinfunction "1_1") (pintype "passive"))
      (node (ref "C16") (pin "1") (pinfunction "1_1") (pintype "passive"))
      (node (ref "C17") (pin "2") (pinfunction "2_2") (pintype "passive"))
      (node (ref "C18") (pin "P$2") (pinfunction "2_P$2") (pintype "passive"))
      (node (ref "C19") (pin "P$2") (pinfunction "2_P$2") (pintype "passive"))
      (node (ref "C2") (pin "P$2") (pinfunction "2_P$2") (pintype "passive"))
      (node (ref "C20") (pin "2") (pinfunction "2_2") (pintype "passive"))
      (node (ref "C21") (pin "P$2") (pinfunction "2_P$2") (pintype "passive"))
      (node (ref "C22") (pin "P$2") (pinfunction "2_P$2") (pintype "passive"))
      (node (ref "C23") (pin "P$2") (pinfunction "2_P$2") (pintype "passive"))
      (node (ref "C24") (pin "P$2") (pinfunction "2_P$2") (pintype "passive"))
      (node (ref "C25") (pin "2") (pinfunction "2_2") (pintype "passive"))
      (node (ref "C26") (pin "2") (pinfunction "2_2") (pintype "passive"))
      (node (ref "C27") (pin "2") (pinfunction "2_2") (pintype "passive"))
      (node (ref "C28") (pin "P$2") (pinfunction "2_P$2") (pintype "passive"))
      (node (ref "C29") (pin "P$2") (pinfunction "2_P$2") (pintype "passive"))
      (node (ref "C3") (pin "P$2") (pinfunction "2_P$2") (pintype "passive"))
      (node (ref "C30") (pin "P$2") (pinfunction "2_P$2") (pintype "passive"))
      (node (ref "C31") (pin "P$2") (pinfunction "2_P$2") (pintype "passive"))
      (node (ref "C32") (pin "P$2") (pinfunction "2_P$2") (pintype "passive"))
      (node (ref "C33") (pin "P$2") (pinfunction "2_P$2") (pintype "passive"))
      (node (ref "C34") (pin "P$2") (pinfunction "2_P$2") (pintype "passive"))
      (node (ref "C35") (pin "P$2") (pinfunction "2_P$2") (pintype "passive"))
      (node (ref "C36") (pin "P$2") (pinfunction "2_P$2") (pintype "passive"))
      (node (ref "C38") (pin "2") (pinfunction "2_2") (pintype "passive"))
      (node (ref "C39") (pin "2") (pinfunction "2_2") (pintype "passive"))
      (node (ref "C4") (pin "P$2") (pinfunction "2_P$2") (pintype "passive"))
      (node (ref "C40") (pin "2") (pinfunction "2_2") (pintype "passive"))
      (node (ref "C41") (pin "2") (pinfunction "2_2") (pintype "passive"))
      (node (ref "C42") (pin "2") (pinfunction "2_2") (pintype "passive"))
      (node (ref "C43") (pin "2") (pinfunction "2_2") (pintype "passive"))
      (node (ref "C44") (pin "2") (pinfunction "2_2") (pintype "passive"))
      (node (ref "C45") (pin "2") (pinfunction "2_2") (pintype "passive"))
      (node (ref "C46") (pin "2") (pinfunction "2_2") (pintype "passive"))
      (node (ref "C47") (pin "2") (pinfunction "2_2") (pintype "passive"))
      (node (ref "C48") (pin "2") (pinfunction "2_2") (pintype "passive"))
      (node (ref "C49") (pin "P$2") (pinfunction "2_P$2") (pintype "passive"))
      (node (ref "C5") (pin "P$2") (pinfunction "2_P$2") (pintype "passive"))
      (node (ref "C50") (pin "2") (pinfunction "2_2") (pintype "passive"))
      (node (ref "C51") (pin "2") (pinfunction "2_2") (pintype "passive"))
      (node (ref "C52") (pin "2") (pinfunction "2_2") (pintype "passive"))
      (node (ref "C53") (pin "2") (pinfunction "2_2") (pintype "passive"))
      (node (ref "C55") (pin "2") (pinfunction "2_2") (pintype "passive"))
      (node (ref "C56") (pin "2") (pinfunction "2_2") (pintype "passive"))
      (node (ref "C57") (pin "2") (pinfunction "2_2") (pintype "passive"))
      (node (ref "C58") (pin "P$2") (pinfunction "2_P$2") (pintype "passive"))
      (node (ref "C59") (pin "P$2") (pinfunction "2_P$2") (pintype "passive"))
      (node (ref "C6") (pin "P$2") (pinfunction "2_P$2") (pintype "passive"))
      (node (ref "C60") (pin "P$2") (pinfunction "2_P$2") (pintype "passive"))
      (node (ref "C61") (pin "P$2") (pinfunction "2_P$2") (pintype "passive"))
      (node (ref "C62") (pin "2") (pinfunction "2_2") (pintype "passive"))
      (node (ref "C7") (pin "P$2") (pinfunction "2_P$2") (pintype "passive"))
      (node (ref "CR4") (pin "A") (pinfunction "A_A") (pintype "bidirectional"))
      (node (ref "D1") (pin "2") (pinfunction "GND_2") (pintype "bidirectional"))
      (node (ref "D10") (pin "2") (pinfunction "GND_2") (pintype "bidirectional"))
      (node (ref "D2") (pin "2") (pinfunction "GND_2") (pintype "bidirectional"))
      (node (ref "J1") (pin "5") (pinfunction "5GND_5") (pintype "bidirectional"))
      (node (ref "J1") (pin "GND") (pinfunction "CASE_GND") (pintype "bidirectional"))
      (node (ref "JP1") (pin "1") (pinfunction "1_1") (pintype "passive"))
      (node (ref "JP2") (pin "3") (pinfunction "3_3") (pintype "passive"))
      (node (ref "L4") (pin "OUT2") (pinfunction "2OUT_OUT2") (pintype "bidirectional"))
      (node (ref "R22") (pin "1") (pinfunction "1_1") (pintype "passive"))
      (node (ref "R28") (pin "1") (pinfunction "1_1") (pintype "passive"))
      (node (ref "R37") (pin "1") (pinfunction "1_1") (pintype "passive"))
      (node (ref "R49") (pin "1") (pinfunction "1_1") (pintype "passive"))
      (node (ref "R50") (pin "1") (pinfunction "1_1") (pintype "passive"))
      (node (ref "R52") (pin "1") (pinfunction "1_1") (pintype "passive"))
      (node (ref "R55") (pin "1") (pinfunction "1_1") (pintype "passive"))
      (node (ref "R57") (pin "1") (pinfunction "1_1") (pintype "passive"))
      (node (ref "R62") (pin "1") (pinfunction "1_1") (pintype "passive"))
      (node (ref "R65") (pin "1") (pinfunction "1_1") (pintype "passive"))
      (node (ref "R67") (pin "1") (pinfunction "1_1") (pintype "passive"))
      (node (ref "R69") (pin "1") (pinfunction "1_1") (pintype "passive"))
      (node (ref "TP1") (pin "P$1") (pinfunction "P$1_P$1") (pintype "bidirectional"))
      (node (ref "TP2") (pin "P$1") (pinfunction "P$1_P$1") (pintype "bidirectional"))
      (node (ref "TP3") (pin "P$1") (pinfunction "P$1_P$1") (pintype "bidirectional"))
      (node (ref "U1") (pin "EP") (pinfunction "GND_EP") (pintype "bidirectional"))
      (node (ref "U2") (pin "EP") (pinfunction "GND_EP") (pintype "bidirectional"))
      (node (ref "U3") (pin "2") (pinfunction "GND_2") (pintype "bidirectional"))
      (node (ref "U4") (pin "1") (pinfunction "GND_1") (pintype "bidirectional"))
      (node (ref "U4") (pin "TP") (pinfunction "GND_TP") (pintype "bidirectional"))
      (node (ref "U5") (pin "3") (pinfunction "GND_3") (pintype "bidirectional"))
      (node (ref "U6") (pin "3") (pinfunction "GND_3") (pintype "bidirectional"))
    )
    (net (code "7") (name "GPIO1-1") (class "Default")
      (node (ref "R28") (pin "2") (pinfunction "2_2") (pintype "passive"))
      (node (ref "U1") (pin "32") (pinfunction "GPIO1_32") (pintype "bidirectional"))
    )
    (net (code "8") (name "GPIO2-1") (class "Default")
      (node (ref "R55") (pin "2") (pinfunction "2_2") (pintype "passive"))
      (node (ref "U1") (pin "8") (pinfunction "GPIO2_8") (pintype "bidirectional"))
    )
    (net (code "9") (name "IN+") (class "Default")
      (node (ref "C14") (pin "2") (pinfunction "2_2") (pintype "passive"))
      (node (ref "D6") (pin "K") (pinfunction "K_K") (pintype "bidirectional"))
      (node (ref "D7") (pin "A") (pinfunction "A_A") (pintype "bidirectional"))
      (node (ref "JP2") (pin "6") (pinfunction "6_6") (pintype "passive"))
      (node (ref "L1") (pin "IN1") (pinfunction "1IN_IN1") (pintype "bidirectional"))
    )
    (net (code "10") (name "IN-") (class "Default")
      (node (ref "C14") (pin "1") (pinfunction "1_1") (pintype "passive"))
      (node (ref "D5") (pin "K") (pinfunction "K_K") (pintype "bidirectional"))
      (node (ref "D8") (pin "A") (pinfunction "A_A") (pintype "bidirectional"))
      (node (ref "JP2") (pin "5") (pinfunction "5_5") (pintype "passive"))
      (node (ref "L1") (pin "OUT2") (pinfunction "2OUT_OUT2") (pintype "bidirectional"))
    )
    (net (code "11") (name "LED0-1") (class "Default")
      (node (ref "CR2") (pin "K") (pinfunction "K_K") (pintype "bidirectional"))
      (node (ref "R26") (pin "1") (pinfunction "1_1") (pintype "passive"))
      (node (ref "U1") (pin "29") (pinfunction "LED_0_29") (pintype "bidirectional"))
    )
    (net (code "12") (name "LED0-2") (class "Default")
      (node (ref "CR3") (pin "K") (pinfunction "K_K") (pintype "bidirectional"))
      (node (ref "R48") (pin "1") (pinfunction "1_1") (pintype "passive"))
      (node (ref "U2") (pin "17") (pinfunction "LED_0_17") (pintype "bidirectional"))
    )
    (net (code "13") (name "LED1-1") (class "Default")
      (node (ref "U1") (pin "30") (pinfunction "CLKOUT/LED_1_30") (pintype "bidirectional"))
    )
    (net (code "14") (name "LED2-1") (class "Default")
      (node (ref "U1") (pin "28") (pinfunction "LED2/TX_ER_28") (pintype "bidirectional"))
    )
    (net (code "15") (name "MDC") (class "Default")
      (node (ref "JP1") (pin "3") (pinfunction "3_3") (pintype "passive"))
      (node (ref "R38") (pin "1") (pinfunction "1_1") (pintype "passive"))
      (node (ref "U1") (pin "12") (pinfunction "MDC_12") (pintype "bidirectional"))
      (node (ref "U2") (pin "20") (pinfunction "MDC_20") (pintype "bidirectional"))
    )
    (net (code "16") (name "MDIO") (class "Default")
      (node (ref "JP1") (pin "4") (pinfunction "4_4") (pintype "passive"))
      (node (ref "R54") (pin "1") (pinfunction "1_1") (pintype "passive"))
      (node (ref "U1") (pin "11") (pinfunction "MDIO_11") (pintype "bidirectional"))
      (node (ref "U2") (pin "19") (pinfunction "MDIO_19") (pintype "bidirectional"))
    )
    (net (code "17") (name "Net-(C1-1)") (class "Default")
      (node (ref "C1") (pin "P$1") (pinfunction "1_P$1") (pintype "passive"))
      (node (ref "C10") (pin "1") (pinfunction "1_1") (pintype "passive"))
      (node (ref "C2") (pin "P$1") (pinfunction "1_P$1") (pintype "passive"))
      (node (ref "C3") (pin "P$1") (pinfunction "1_P$1") (pintype "passive"))
      (node (ref "R1") (pin "1") (pinfunction "1_1") (pintype "passive"))
      (node (ref "U1") (pin "3") (pinfunction "VDDA_3") (pintype "bidirectional"))
    )
    (net (code "18") (name "Net-(C4-1)") (class "Default")
      (node (ref "C25") (pin "1") (pinfunction "1_1") (pintype "passive"))
      (node (ref "C4") (pin "P$1") (pinfunction "1_P$1") (pintype "passive"))
      (node (ref "C5") (pin "P$1") (pinfunction "1_P$1") (pintype "passive"))
      (node (ref "C6") (pin "P$1") (pinfunction "1_P$1") (pintype "passive"))
      (node (ref "R2") (pin "1") (pinfunction "1_1") (pintype "passive"))
      (node (ref "U1") (pin "17") (pinfunction "VDDIO_17") (pintype "bidirectional"))
    )
    (net (code "19") (name "Net-(C7-1)") (class "Default")
      (node (ref "C7") (pin "P$1") (pinfunction "1_P$1") (pintype "passive"))
      (node (ref "U1") (pin "1") (pinfunction "DVDD_1.0_1") (pintype "bidirectional"))
      (node (ref "U1") (pin "2") (pinfunction "CEXT_2") (pintype "bidirectional"))
    )
    (net (code "20") (name "Net-(C8-Pad2)") (class "Default")
      (node (ref "C8") (pin "2") (pinfunction "2_2") (pintype "passive"))
      (node (ref "T1") (pin "1") (pinfunction "1_1") (pintype "bidirectional"))
    )
    (net (code "21") (name "Net-(C11-Pad2)") (class "Default")
      (node (ref "C11") (pin "2") (pinfunction "2_2") (pintype "passive"))
      (node (ref "R25") (pin "1") (pinfunction "1_1") (pintype "passive"))
    )
    (net (code "22") (name "Net-(C12-Pad1)") (class "Default")
      (node (ref "C12") (pin "1") (pinfunction "1_1") (pintype "passive"))
      (node (ref "R36") (pin "1") (pinfunction "1_1") (pintype "passive"))
    )
    (net (code "23") (name "Net-(C13-Pad1)") (class "Default")
      (node (ref "C13") (pin "1") (pinfunction "1_1") (pintype "passive"))
      (node (ref "R35") (pin "1") (pinfunction "1_1") (pintype "passive"))
    )
    (net (code "24") (name "Net-(C18-1)") (class "Default")
      (node (ref "C18") (pin "P$1") (pinfunction "1_P$1") (pintype "passive"))
      (node (ref "C19") (pin "P$1") (pinfunction "1_P$1") (pintype "passive"))
      (node (ref "C21") (pin "P$1") (pinfunction "1_P$1") (pintype "passive"))
      (node (ref "C27") (pin "1") (pinfunction "1_1") (pintype "passive"))
      (node (ref "R42") (pin "1") (pinfunction "1_1") (pintype "passive"))
      (node (ref "U2") (pin "21") (pinfunction "VDDIO_21") (pintype "bidirectional"))
    )
    (net (code "25") (name "Net-(C20-Pad1)") (class "Default")
      (node (ref "C20") (pin "1") (pinfunction "1_1") (pintype "passive"))
      (node (ref "C47") (pin "1") (pinfunction "1_1") (pintype "passive"))
      (node (ref "C55") (pin "1") (pinfunction "1_1") (pintype "passive"))
      (node (ref "C56") (pin "1") (pinfunction "1_1") (pintype "passive"))
      (node (ref "C57") (pin "1") (pinfunction "1_1") (pintype "passive"))
      (node (ref "L6") (pin "P$1") (pinfunction "P$1_P$1") (pintype "bidirectional"))
      (node (ref "R68") (pin "2") (pinfunction "2_2") (pintype "passive"))
      (node (ref "R70") (pin "1") (pinfunction "1_1") (pintype "passive"))
    )
    (net (code "26") (name "Net-(C22-1)") (class "Default")
      (node (ref "C22") (pin "P$1") (pinfunction "1_P$1") (pintype "passive"))
      (node (ref "C23") (pin "P$1") (pinfunction "1_P$1") (pintype "passive"))
      (node (ref "C26") (pin "1") (pinfunction "1_1") (pintype "passive"))
      (node (ref "C49") (pin "P$1") (pinfunction "1_P$1") (pintype "passive"))
      (node (ref "R43") (pin "1") (pinfunction "1_1") (pintype "passive"))
      (node (ref "U2") (pin "14") (pinfunction "AVD_14") (pintype "bidirectional"))
    )
    (net (code "27") (name "Net-(C24-1)") (class "Default")
      (node (ref "C24") (pin "P$1") (pinfunction "1_P$1") (pintype "passive"))
      (node (ref "R46") (pin "1") (pinfunction "1_1") (pintype "passive"))
      (node (ref "U3") (pin "4") (pinfunction "VCC_4") (pintype "bidirectional"))
    )
    (net (code "28") (name "Net-(CR1-PadK)") (class "Default")
      (node (ref "CR1") (pin "K") (pinfunction "K_K") (pintype "bidirectional"))
      (node (ref "R22") (pin "2") (pinfunction "2_2") (pintype "passive"))
    )
    (net (code "29") (name "Net-(CR2-PadA)") (class "Default")
      (node (ref "CR2") (pin "A") (pinfunction "A_A") (pintype "bidirectional"))
      (node (ref "R34") (pin "1") (pinfunction "1_1") (pintype "passive"))
    )
    (net (code "30") (name "Net-(CR3-PadA)") (class "Default")
      (node (ref "CR3") (pin "A") (pinfunction "A_A") (pintype "bidirectional"))
      (node (ref "R17") (pin "1") (pinfunction "1_1") (pintype "passive"))
    )
    (net (code "31") (name "Net-(D1-IO1)") (class "Default")
      (node (ref "D1") (pin "5") (pinfunction "IO1_5") (pintype "bidirectional"))
      (node (ref "R16") (pin "1") (pinfunction "1_1") (pintype "passive"))
      (node (ref "T4") (pin "3") (pinfunction "1N_PHY_3") (pintype "bidirectional"))
      (node (ref "U2") (pin "11") (pinfunction "TD_M_11") (pintype "bidirectional"))
    )
    (net (code "32") (name "Net-(D1-IO2)") (class "Default")
      (node (ref "D1") (pin "4") (pinfunction "IO2_4") (pintype "bidirectional"))
      (node (ref "R15") (pin "2") (pinfunction "2_2") (pintype "passive"))
      (node (ref "T4") (pin "1") (pinfunction "1P_PHY_1") (pintype "bidirectional"))
      (node (ref "U2") (pin "12") (pinfunction "TD_P_12") (pintype "bidirectional"))
    )
    (net (code "33") (name "Net-(D2-IO1)") (class "Default")
      (node (ref "D2") (pin "5") (pinfunction "IO1_5") (pintype "bidirectional"))
      (node (ref "R56") (pin "1") (pinfunction "1_1") (pintype "passive"))
      (node (ref "T4") (pin "8") (pinfunction "2N_PHY_8") (pintype "bidirectional"))
      (node (ref "U2") (pin "9") (pinfunction "RD_M_9") (pintype "bidirectional"))
    )
    (net (code "34") (name "Net-(D2-IO2)") (class "Default")
      (node (ref "D2") (pin "4") (pinfunction "IO2_4") (pintype "bidirectional"))
      (node (ref "R18") (pin "2") (pinfunction "2_2") (pintype "passive"))
      (node (ref "T4") (pin "6") (pinfunction "2P_PHY_6") (pintype "bidirectional"))
      (node (ref "U2") (pin "10") (pinfunction "RD_P_10") (pintype "bidirectional"))
    )
    (net (code "35") (name "Net-(D10-IO1)") (class "Default")
      (node (ref "D10") (pin "5") (pinfunction "IO1_5") (pintype "bidirectional"))
      (node (ref "R21") (pin "1") (pinfunction "1_1") (pintype "passive"))
      (node (ref "R23") (pin "1") (pinfunction "1_1") (pintype "passive"))
      (node (ref "T1") (pin "5") (pinfunction "6_5") (pintype "bidirectional"))
    )
    (net (code "36") (name "Net-(D10-IO2)") (class "Default")
      (node (ref "D10") (pin "4") (pinfunction "IO2_4") (pintype "bidirectional"))
      (node (ref "R19") (pin "1") (pinfunction "1_1") (pintype "passive"))
      (node (ref "R20") (pin "1") (pinfunction "1_1") (pintype "passive"))
      (node (ref "T1") (pin "4") (pinfunction "4_4") (pintype "bidirectional"))
    )
    (net (code "37") (name "Net-(D10-VCC)") (class "Default")
      (node (ref "C15") (pin "2") (pinfunction "2_2") (pintype "passive"))
      (node (ref "D10") (pin "3") (pinfunction "VCC_3") (pintype "bidirectional"))
      (node (ref "R24") (pin "1") (pinfunction "1_1") (pintype "passive"))
    )
    (net (code "38") (name "Net-(F2-P$1)") (class "Default")
      (node (ref "D4") (pin "K") (pinfunction "K_K") (pintype "bidirectional"))
      (node (ref "F2") (pin "1") (pinfunction "P$1_1") (pintype "bidirectional"))
    )
    (net (code "39") (name "Net-(J1-1VCC)") (class "Default")
      (node (ref "D3") (pin "A") (pinfunction "A_A") (pintype "bidirectional"))
      (node (ref "J1") (pin "1") (pinfunction "1VCC_1") (pintype "bidirectional"))
    )
    (net (code "40") (name "Net-(J2-Pad4)") (class "Default")
      (node (ref "J2") (pin "4") (pinfunction "4_4") (pintype "bidirectional"))
      (node (ref "J2") (pin "5") (pinfunction "5_5") (pintype "bidirectional"))
      (node (ref "R63") (pin "2") (pinfunction "2_2") (pintype "passive"))
    )
    (net (code "41") (name "Net-(J2-Pad7)") (class "Default")
      (node (ref "J2") (pin "7") (pinfunction "7_7") (pintype "bidirectional"))
      (node (ref "J2") (pin "8") (pinfunction "8_8") (pintype "bidirectional"))
      (node (ref "R60") (pin "2") (pinfunction "2_2") (pintype "passive"))
    )
    (net (code "42") (name "Net-(L1-1OUT)") (class "Default")
      (node (ref "C9") (pin "2") (pinfunction "2_2") (pintype "passive"))
      (node (ref "L1") (pin "OUT1") (pinfunction "1OUT_OUT1") (pintype "bidirectional"))
      (node (ref "L3") (pin "OUT2") (pinfunction "2OUT_OUT2") (pintype "bidirectional"))
      (node (ref "R35") (pin "2") (pinfunction "2_2") (pintype "passive"))
    )
    (net (code "43") (name "Net-(L1-2IN)") (class "Default")
      (node (ref "C8") (pin "1") (pinfunction "1_1") (pintype "passive"))
      (node (ref "L1") (pin "IN2") (pinfunction "2IN_IN2") (pintype "bidirectional"))
      (node (ref "L3") (pin "OUT1") (pinfunction "1OUT_OUT1") (pintype "bidirectional"))
      (node (ref "R36") (pin "2") (pinfunction "2_2") (pintype "passive"))
    )
    (net (code "44") (name "Net-(L3-1IN)") (class "Default")
      (node (ref "J3") (pin "2A") (pinfunction "2_2A") (pintype "bidirectional"))
      (node (ref "J3") (pin "2B") (pinfunction "2_2B") (pintype "bidirectional"))
      (node (ref "L3") (pin "IN1") (pinfunction "1IN_IN1") (pintype "bidirectional"))
    )
    (net (code "45") (name "Net-(L3-2IN)") (class "Default")
      (node (ref "J3") (pin "1A") (pinfunction "1_1A") (pintype "bidirectional"))
      (node (ref "J3") (pin "1B") (pinfunction "1_1B") (pintype "bidirectional"))
      (node (ref "L3") (pin "IN2") (pinfunction "2IN_IN2") (pintype "bidirectional"))
    )
    (net (code "46") (name "Net-(L4-1IN)") (class "Default")
      (node (ref "J4") (pin "2A") (pinfunction "2_2A") (pintype "bidirectional"))
      (node (ref "J4") (pin "2B") (pinfunction "2_2B") (pintype "bidirectional"))
      (node (ref "L4") (pin "IN1") (pinfunction "1IN_IN1") (pintype "bidirectional"))
    )
    (net (code "47") (name "Net-(L4-1OUT)") (class "Default")
      (node (ref "C48") (pin "1") (pinfunction "1_1") (pintype "passive"))
      (node (ref "D4") (pin "A") (pinfunction "A_A") (pintype "bidirectional"))
      (node (ref "L4") (pin "OUT1") (pinfunction "1OUT_OUT1") (pintype "bidirectional"))
    )
    (net (code "48") (name "Net-(L4-2IN)") (class "Default")
      (node (ref "J4") (pin "1A") (pinfunction "1_1A") (pintype "bidirectional"))
      (node (ref "J4") (pin "1B") (pinfunction "1_1B") (pintype "bidirectional"))
      (node (ref "L4") (pin "IN2") (pinfunction "2IN_IN2") (pintype "bidirectional"))
    )
    (net (code "49") (name "Net-(T1-2)") (class "Default")
      (node (ref "R25") (pin "2") (pinfunction "2_2") (pintype "passive"))
      (node (ref "T1") (pin "6") (pinfunction "2_6") (pintype "bidirectional"))
    )
    (net (code "50") (name "Net-(T1-3)") (class "Default")
      (node (ref "C9") (pin "1") (pinfunction "1_1") (pintype "passive"))
      (node (ref "T1") (pin "2") (pinfunction "3_2") (pintype "bidirectional"))
    )
    (net (code "51") (name "Net-(T1-5)") (class "Default")
      (node (ref "C16") (pin "2") (pinfunction "2_2") (pintype "passive"))
      (node (ref "T1") (pin "3") (pinfunction "5_3") (pintype "bidirectional"))
    )
    (net (code "52") (name "Net-(T4-1C)") (class "Default")
      (node (ref "R32") (pin "1") (pinfunction "1_1") (pintype "passive"))
      (node (ref "T4") (pin "15") (pinfunction "1C_15") (pintype "bidirectional"))
    )
    (net (code "53") (name "Net-(T4-2C)") (class "Default")
      (node (ref "R33") (pin "1") (pinfunction "1_1") (pintype "passive"))
      (node (ref "T4") (pin "10") (pinfunction "2C_10") (pintype "bidirectional"))
    )
    (net (code "54") (name "Net-(U1-PWDN{slash}INT)") (class "Default")
      (node (ref "R31") (pin "1") (pinfunction "1_1") (pintype "passive"))
      (node (ref "U1") (pin "21") (pinfunction "PWDN/INT_21") (pintype "bidirectional"))
    )
    (net (code "55") (name "Net-(U1-RX+)") (class "Default")
      (node (ref "R20") (pin "2") (pinfunction "2_2") (pintype "passive"))
      (node (ref "U1") (pin "5") (pinfunction "RX+_5") (pintype "bidirectional"))
    )
    (net (code "56") (name "Net-(U1-RX-)") (class "Default")
      (node (ref "R21") (pin "2") (pinfunction "2_2") (pintype "passive"))
      (node (ref "U1") (pin "6") (pinfunction "RX-_6") (pintype "bidirectional"))
    )
    (net (code "57") (name "Net-(U1-TX+)") (class "Default")
      (node (ref "R19") (pin "2") (pinfunction "2_2") (pintype "passive"))
      (node (ref "U1") (pin "4") (pinfunction "TX+_4") (pintype "bidirectional"))
    )
    (net (code "58") (name "Net-(U1-TX-)") (class "Default")
      (node (ref "R23") (pin "2") (pinfunction "2_2") (pintype "passive"))
      (node (ref "U1") (pin "7") (pinfunction "TX-_7") (pintype "bidirectional"))
    )
    (net (code "59") (name "Net-(U1-XI{slash}50M)") (class "Default")
      (node (ref "R45") (pin "2") (pinfunction "2_2") (pintype "passive"))
      (node (ref "U1") (pin "10") (pinfunction "XI/50M_10") (pintype "bidirectional"))
    )
    (net (code "60") (name "Net-(U2-RBIAS)") (class "Default")
      (node (ref "R37") (pin "2") (pinfunction "2_2") (pintype "passive"))
      (node (ref "U2") (pin "16") (pinfunction "RBIAS_16") (pintype "bidirectional"))
    )
    (net (code "61") (name "Net-(U2-RX_CLK)") (class "Default")
      (node (ref "R14") (pin "2") (pinfunction "2_2") (pintype "passive"))
      (node (ref "U2") (pin "25") (pinfunction "RX_CLK_25") (pintype "bidirectional"))
    )
    (net (code "62") (name "Net-(U2-RX_DV{slash}RX_CTRL)") (class "Default")
      (node (ref "R12") (pin "2") (pinfunction "2_2") (pintype "passive"))
      (node (ref "U2") (pin "26") (pinfunction "RX_DV/RX_CTRL_26") (pintype "bidirectional"))
    )
    (net (code "63") (name "Net-(U2-TX_D0)") (class "Default")
      (node (ref "R3") (pin "2") (pinfunction "2_2") (pintype "passive"))
      (node (ref "U2") (pin "4") (pinfunction "TX_D0_4") (pintype "bidirectional"))
    )
    (net (code "64") (name "Net-(U2-TX_D1)") (class "Default")
      (node (ref "R4") (pin "2") (pinfunction "2_2") (pintype "passive"))
      (node (ref "U2") (pin "5") (pinfunction "TX_D1_5") (pintype "bidirectional"))
    )
    (net (code "65") (name "Net-(U2-TX_D2)") (class "Default")
      (node (ref "R5") (pin "2") (pinfunction "2_2") (pintype "passive"))
      (node (ref "U2") (pin "6") (pinfunction "TX_D2_6") (pintype "bidirectional"))
    )
    (net (code "66") (name "Net-(U2-TX_D3)") (class "Default")
      (node (ref "R6") (pin "2") (pinfunction "2_2") (pintype "passive"))
      (node (ref "U2") (pin "7") (pinfunction "TX_D3_7") (pintype "bidirectional"))
    )
    (net (code "67") (name "Net-(U2-TX_EN{slash}TX_CTRL)") (class "Default")
      (node (ref "R11") (pin "2") (pinfunction "2_2") (pintype "passive"))
      (node (ref "U2") (pin "3") (pinfunction "TX_EN/TX_CTRL_3") (pintype "bidirectional"))
    )
    (net (code "68") (name "Net-(U2-XI)") (class "Default")
      (node (ref "R41") (pin "2") (pinfunction "2_2") (pintype "passive"))
      (node (ref "R44") (pin "2") (pinfunction "2_2") (pintype "passive"))
      (node (ref "U2") (pin "23") (pinfunction "XI_23") (pintype "bidirectional"))
    )
    (net (code "69") (name "Net-(U2-~{INT{slash}PWDN})") (class "Default")
      (node (ref "R39") (pin "1") (pinfunction "1_1") (pintype "passive"))
      (node (ref "U2") (pin "8") (pinfunction "~{INT/PWDN}_8") (pintype "bidirectional"))
    )
    (net (code "70") (name "Net-(U3-OUT)") (class "Default")
      (node (ref "R44") (pin "1") (pinfunction "1_1") (pintype "passive"))
      (node (ref "R45") (pin "1") (pinfunction "1_1") (pintype "passive"))
      (node (ref "U3") (pin "3") (pinfunction "OUT_3") (pintype "bidirectional"))
    )
    (net (code "71") (name "Net-(U4-BOOT)") (class "Default")
      (node (ref "C54") (pin "1") (pinfunction "1_1") (pintype "passive"))
      (node (ref "U4") (pin "7") (pinfunction "BOOT_7") (pintype "bidirectional"))
    )
    (net (code "72") (name "Net-(U4-EN)") (class "Default")
      (node (ref "R62") (pin "2") (pinfunction "2_2") (pintype "passive"))
      (node (ref "R66") (pin "1") (pinfunction "1_1") (pintype "passive"))
      (node (ref "U4") (pin "2") (pinfunction "EN_2") (pintype "bidirectional"))
    )
    (net (code "73") (name "Net-(U4-FB)") (class "Default")
      (node (ref "R68") (pin "1") (pinfunction "1_1") (pintype "passive"))
      (node (ref "R69") (pin "2") (pinfunction "2_2") (pintype "passive"))
      (node (ref "U4") (pin "5") (pinfunction "FB_5") (pintype "bidirectional"))
    )
    (net (code "74") (name "Net-(U4-RT)") (class "Default")
      (node (ref "R67") (pin "2") (pinfunction "2_2") (pintype "passive"))
      (node (ref "U4") (pin "4") (pinfunction "RT_4") (pintype "bidirectional"))
    )
    (net (code "75") (name "Net-(U4-SW)") (class "Default")
      (node (ref "C54") (pin "2") (pinfunction "2_2") (pintype "passive"))
      (node (ref "L6") (pin "P$2") (pinfunction "P$2_P$2") (pintype "bidirectional"))
      (node (ref "U4") (pin "8") (pinfunction "SW_8") (pintype "bidirectional"))
    )
    (net (code "76") (name "Net-(U4-VIN)") (class "Default")
      (node (ref "C17") (pin "1") (pinfunction "1_1") (pintype "passive"))
      (node (ref "C38") (pin "1") (pinfunction "1_1") (pintype "passive"))
      (node (ref "C39") (pin "1") (pinfunction "1_1") (pintype "passive"))
      (node (ref "C40") (pin "1") (pinfunction "1_1") (pintype "passive"))
      (node (ref "C41") (pin "1") (pinfunction "1_1") (pintype "passive"))
      (node (ref "C42") (pin "1") (pinfunction "1_1") (pintype "passive"))
      (node (ref "C43") (pin "1") (pinfunction "1_1") (pintype "passive"))
      (node (ref "C44") (pin "1") (pinfunction "1_1") (pintype "passive"))
      (node (ref "C45") (pin "1") (pinfunction "1_1") (pintype "passive"))
      (node (ref "C46") (pin "1") (pinfunction "1_1") (pintype "passive"))
      (node (ref "C50") (pin "1") (pinfunction "1_1") (pintype "passive"))
      (node (ref "C51") (pin "1") (pinfunction "1_1") (pintype "passive"))
      (node (ref "C52") (pin "1") (pinfunction "1_1") (pintype "passive"))
      (node (ref "R64") (pin "2") (pinfunction "2_2") (pintype "passive"))
      (node (ref "R66") (pin "2") (pinfunction "2_2") (pintype "passive"))
      (node (ref "U4") (pin "3") (pinfunction "VIN_3") (pintype "bidirectional"))
    )
    (net (code "77") (name "RST_N") (class "Default")
      (node (ref "U4") (pin "6") (pinfunction "PG_6") (pintype "bidirectional"))
    )
    (net (code "78") (name "RTN") (class "Default")
      (node (ref "D5") (pin "A") (pinfunction "A_A") (pintype "bidirectional"))
      (node (ref "D6") (pin "A") (pinfunction "A_A") (pintype "bidirectional"))
      (node (ref "JP2") (pin "1") (pinfunction "1_1") (pintype "passive"))
    )
    (net (code "79") (name "RX_CLK-1") (class "Default")
      (node (ref "R13") (pin "1") (pinfunction "1_1") (pintype "passive"))
      (node (ref "U1") (pin "19") (pinfunction "RX_CLK/50M_RMII_19") (pintype "bidirectional"))
    )
    (net (code "80") (name "RX_D0-1") (class "Default")
      (node (ref "R3") (pin "1") (pinfunction "1_1") (pintype "passive"))
      (node (ref "U1") (pin "16") (pinfunction "RX_D0_16") (pintype "bidirectional"))
    )
    (net (code "81") (name "RX_D0-2") (class "Default")
      (node (ref "R49") (pin "2") (pinfunction "2_2") (pintype "passive"))
      (node (ref "R53") (pin "1") (pinfunction "1_1") (pintype "passive"))
      (node (ref "R7") (pin "2") (pinfunction "2_2") (pintype "passive"))
      (node (ref "U2") (pin "30") (pinfunction "RX_D0_30") (pintype "bidirectional"))
    )
    (net (code "82") (name "RX_D1-1") (class "Default")
      (node (ref "R29") (pin "1") (pinfunction "1_1") (pintype "passive"))
      (node (ref "R4") (pin "1") (pinfunction "1_1") (pintype "passive"))
      (node (ref "U1") (pin "15") (pinfunction "RX_D1_15") (pintype "bidirectional"))
    )
    (net (code "83") (name "RX_D1-2") (class "Default")
      (node (ref "R47") (pin "1") (pinfunction "1_1") (pintype "passive"))
      (node (ref "R8") (pin "2") (pinfunction "2_2") (pintype "passive"))
      (node (ref "U2") (pin "31") (pinfunction "RX_D1_31") (pintype "bidirectional"))
    )
    (net (code "84") (name "RX_D2-1") (class "Default")
      (node (ref "R30") (pin "1") (pinfunction "1_1") (pintype "passive"))
      (node (ref "R5") (pin "1") (pinfunction "1_1") (pintype "passive"))
      (node (ref "U1") (pin "14") (pinfunction "RX_D2_14") (pintype "bidirectional"))
    )
    (net (code "85") (name "RX_D2-2") (class "Default")
      (node (ref "R9") (pin "2") (pinfunction "2_2") (pintype "passive"))
      (node (ref "U2") (pin "32") (pinfunction "RX_D2_32") (pintype "bidirectional"))
    )
    (net (code "86") (name "RX_D3-1") (class "Default")
      (node (ref "R6") (pin "1") (pinfunction "1_1") (pintype "passive"))
      (node (ref "U1") (pin "13") (pinfunction "RX_D3_13") (pintype "bidirectional"))
    )
    (net (code "87") (name "RX_D3-2") (class "Default")
      (node (ref "R10") (pin "2") (pinfunction "2_2") (pintype "passive"))
      (node (ref "U2") (pin "1") (pinfunction "RX_D3_1") (pintype "bidirectional"))
    )
    (net (code "88") (name "RX_DV-1") (class "Default")
      (node (ref "R11") (pin "1") (pinfunction "1_1") (pintype "passive"))
      (node (ref "R27") (pin "1") (pinfunction "1_1") (pintype "passive"))
      (node (ref "U1") (pin "18") (pinfunction "RX_DV/CRS_DV_18") (pintype "bidirectional"))
    )
    (net (code "89") (name "RX_ER-1") (class "Default")
      (node (ref "U1") (pin "20") (pinfunction "RX_ER_20") (pintype "bidirectional"))
    )
    (net (code "90") (name "RX_ER-2") (class "Default")
      (node (ref "R51") (pin "1") (pinfunction "1_1") (pintype "passive"))
      (node (ref "R52") (pin "2") (pinfunction "2_2") (pintype "passive"))
      (node (ref "U2") (pin "28") (pinfunction "RX_ER_28") (pintype "bidirectional"))
    )
    (net (code "91") (name "RX_N") (class "Default")
      (node (ref "J2") (pin "2") (pinfunction "2_2") (pintype "bidirectional"))
      (node (ref "T4") (pin "9") (pinfunction "2N_9") (pintype "bidirectional"))
    )
    (net (code "92") (name "RX_P") (class "Default")
      (node (ref "J2") (pin "1") (pinfunction "1_1") (pintype "bidirectional"))
      (node (ref "T4") (pin "11") (pinfunction "2P_11") (pintype "bidirectional"))
    )
    (net (code "93") (name "TCT") (class "Default")
      (node (ref "C29") (pin "P$1") (pinfunction "1_P$1") (pintype "passive"))
      (node (ref "C31") (pin "P$1") (pinfunction "1_P$1") (pintype "passive"))
      (node (ref "C32") (pin "P$1") (pinfunction "1_P$1") (pintype "passive"))
      (node (ref "C33") (pin "P$1") (pinfunction "1_P$1") (pintype "passive"))
      (node (ref "C34") (pin "P$1") (pinfunction "1_P$1") (pintype "passive"))
      (node (ref "C35") (pin "P$1") (pinfunction "1_P$1") (pintype "passive"))
      (node (ref "C36") (pin "P$1") (pinfunction "1_P$1") (pintype "passive"))
      (node (ref "C58") (pin "P$1") (pinfunction "1_P$1") (pintype "passive"))
      (node (ref "D1") (pin "3") (pinfunction "VCC_3") (pintype "bidirectional"))
      (node (ref "D2") (pin "3") (pinfunction "VCC_3") (pintype "bidirectional"))
      (node (ref "R15") (pin "1") (pinfunction "1_1") (pintype "passive"))
      (node (ref "R16") (pin "2") (pinfunction "2_2") (pintype "passive"))
      (node (ref "R18") (pin "1") (pinfunction "1_1") (pintype "passive"))
      (node (ref "R56") (pin "2") (pinfunction "2_2") (pintype "passive"))
      (node (ref "R61") (pin "1") (pinfunction "1_1") (pintype "passive"))
      (node (ref "T4") (pin "2") (pinfunction "1C_PHY_2") (pintype "bidirectional"))
      (node (ref "T4") (pin "7") (pinfunction "2C_PHY_7") (pintype "bidirectional"))
    )
    (net (code "94") (name "TX_CLK-1") (class "Default")
      (node (ref "R59") (pin "1") (pinfunction "1_1") (pintype "passive"))
      (node (ref "U1") (pin "22") (pinfunction "TX_CLK_22") (pintype "bidirectional"))
      (node (ref "U5") (pin "4") (pinfunction "OUT_4") (pintype "bidirectional"))
    )
    (net (code "95") (name "TX_CLK-1_RC") (class "Default")
      (node (ref "C30") (pin "P$1") (pinfunction "1_P$1") (pintype "passive"))
      (node (ref "R14") (pin "1") (pinfunction "1_1") (pintype "passive"))
      (node (ref "R59") (pin "2") (pinfunction "2_2") (pintype "passive"))
      (node (ref "U5") (pin "2") (pinfunction "IN_2") (pintype "bidirectional"))
    )
    (net (code "96") (name "TX_CLK-2") (class "Default")
      (node (ref "R41") (pin "1") (pinfunction "1_1") (pintype "passive"))
      (node (ref "R58") (pin "2") (pinfunction "2_2") (pintype "passive"))
      (node (ref "U2") (pin "2") (pinfunction "TX_CLK_2") (pintype "bidirectional"))
      (node (ref "U6") (pin "4") (pinfunction "OUT_4") (pintype "bidirectional"))
    )
    (net (code "97") (name "TX_CLK-2_RC") (class "Default")
      (node (ref "C28") (pin "P$1") (pinfunction "1_P$1") (pintype "passive"))
      (node (ref "R13") (pin "2") (pinfunction "2_2") (pintype "passive"))
      (node (ref "R58") (pin "1") (pinfunction "1_1") (pintype "passive"))
      (node (ref "U6") (pin "2") (pinfunction "IN_2") (pintype "bidirectional"))
    )
    (net (code "98") (name "TX_D0-1") (class "Default")
      (node (ref "R7") (pin "1") (pinfunction "1_1") (pintype "passive"))
      (node (ref "U1") (pin "24") (pinfunction "TX_D0_24") (pintype "bidirectional"))
    )
    (net (code "99") (name "TX_D1-1") (class "Default")
      (node (ref "R8") (pin "1") (pinfunction "1_1") (pintype "passive"))
      (node (ref "U1") (pin "25") (pinfunction "TX_D1_25") (pintype "bidirectional"))
    )
    (net (code "100") (name "TX_D2-1") (class "Default")
      (node (ref "R9") (pin "1") (pinfunction "1_1") (pintype "passive"))
      (node (ref "U1") (pin "26") (pinfunction "TX_D2_26") (pintype "bidirectional"))
    )
    (net (code "101") (name "TX_D3-1") (class "Default")
      (node (ref "R10") (pin "1") (pinfunction "1_1") (pintype "passive"))
      (node (ref "U1") (pin "27") (pinfunction "TX_D3_27") (pintype "bidirectional"))
    )
    (net (code "102") (name "TX_EN-1") (class "Default")
      (node (ref "R12") (pin "1") (pinfunction "1_1") (pintype "passive"))
      (node (ref "U1") (pin "23") (pinfunction "TX_EN_23") (pintype "bidirectional"))
    )
    (net (code "103") (name "TX_N") (class "Default")
      (node (ref "J2") (pin "6") (pinfunction "6_6") (pintype "bidirectional"))
      (node (ref "T4") (pin "14") (pinfunction "1N_14") (pintype "bidirectional"))
    )
    (net (code "104") (name "TX_P") (class "Default")
      (node (ref "J2") (pin "3") (pinfunction "3_3") (pintype "bidirectional"))
      (node (ref "T4") (pin "16") (pinfunction "1P_16") (pintype "bidirectional"))
    )
    (net (code "105") (name "V+") (class "Default")
      (node (ref "CR4") (pin "C") (pinfunction "K_C") (pintype "bidirectional"))
      (node (ref "D3") (pin "K") (pinfunction "K_K") (pintype "bidirectional"))
      (node (ref "F1") (pin "2") (pinfunction "P$2_2") (pintype "bidirectional"))
      (node (ref "F2") (pin "2") (pinfunction "P$2_2") (pintype "bidirectional"))
      (node (ref "R64") (pin "1") (pinfunction "1_1") (pintype "passive"))
      (node (ref "TP4") (pin "P$1") (pinfunction "P$1_P$1") (pintype "bidirectional"))
    )
    (net (code "106") (name "V+F") (class "Default")
      (node (ref "F1") (pin "1") (pinfunction "P$1_1") (pintype "bidirectional"))
      (node (ref "JP2") (pin "4") (pinfunction "4_4") (pintype "passive"))
    )
    (net (code "107") (name "VIN") (class "Default")
      (node (ref "D7") (pin "K") (pinfunction "K_K") (pintype "bidirectional"))
      (node (ref "D8") (pin "K") (pinfunction "K_K") (pintype "bidirectional"))
      (node (ref "JP2") (pin "2") (pinfunction "2_2") (pintype "passive"))
    )
    (net (code "108") (name "unconnected-(J1-2DM-Pad2)") (class "Default")
      (node (ref "J1") (pin "2") (pinfunction "2DM_2") (pintype "bidirectional"))
    )
    (net (code "109") (name "unconnected-(J1-3DP-Pad3)") (class "Default")
      (node (ref "J1") (pin "3") (pinfunction "3DP_3") (pintype "bidirectional"))
    )
    (net (code "110") (name "unconnected-(J1-4ID-Pad4)") (class "Default")
      (node (ref "J1") (pin "4") (pinfunction "4ID_4") (pintype "bidirectional"))
    )
    (net (code "111") (name "unconnected-(U1-XO-Pad9)") (class "Default")
      (node (ref "U1") (pin "9") (pinfunction "XO_9") (pintype "bidirectional"))
    )
    (net (code "112") (name "unconnected-(U2-COL{slash}GPIO2-Pad29)") (class "Default")
      (node (ref "U2") (pin "29") (pinfunction "COL/GPIO2_29") (pintype "bidirectional"))
    )
    (net (code "113") (name "unconnected-(U2-LED1{slash}GPIO1-Pad24)") (class "Default")
      (node (ref "U2") (pin "24") (pinfunction "LED1/GPIO1_24") (pintype "bidirectional"))
    )
    (net (code "114") (name "unconnected-(U2-NC1-Pad13)") (class "Default")
      (node (ref "U2") (pin "13") (pinfunction "NC1_13") (pintype "bidirectional"))
    )
    (net (code "115") (name "unconnected-(U2-NC2-Pad15)") (class "Default")
      (node (ref "U2") (pin "15") (pinfunction "NC2_15") (pintype "bidirectional"))
    )
    (net (code "116") (name "unconnected-(U2-XO-Pad22)") (class "Default")
      (node (ref "U2") (pin "22") (pinfunction "XO_22") (pintype "bidirectional"))
    )
    (net (code "117") (name "unconnected-(U3-NC-Pad1)") (class "Default")
      (node (ref "U3") (pin "1") (pinfunction "NC_1") (pintype "bidirectional"))
    )
    (net (code "118") (name "~{RST}") (class "Default")
      (node (ref "C61") (pin "P$1") (pinfunction "1_P$1") (pintype "passive"))
      (node (ref "JP1") (pin "2") (pinfunction "2_2") (pintype "passive"))
      (node (ref "R40") (pin "1") (pinfunction "1_1") (pintype "passive"))
      (node (ref "U1") (pin "31") (pinfunction "~{RST_N}_31") (pintype "bidirectional"))
      (node (ref "U2") (pin "18") (pinfunction "~{RESET\\}_18") (pintype "bidirectional"))
    )
  )
)
